# SAS_rev04.net
KiCad netlist of a schematic drawn in EAGLE
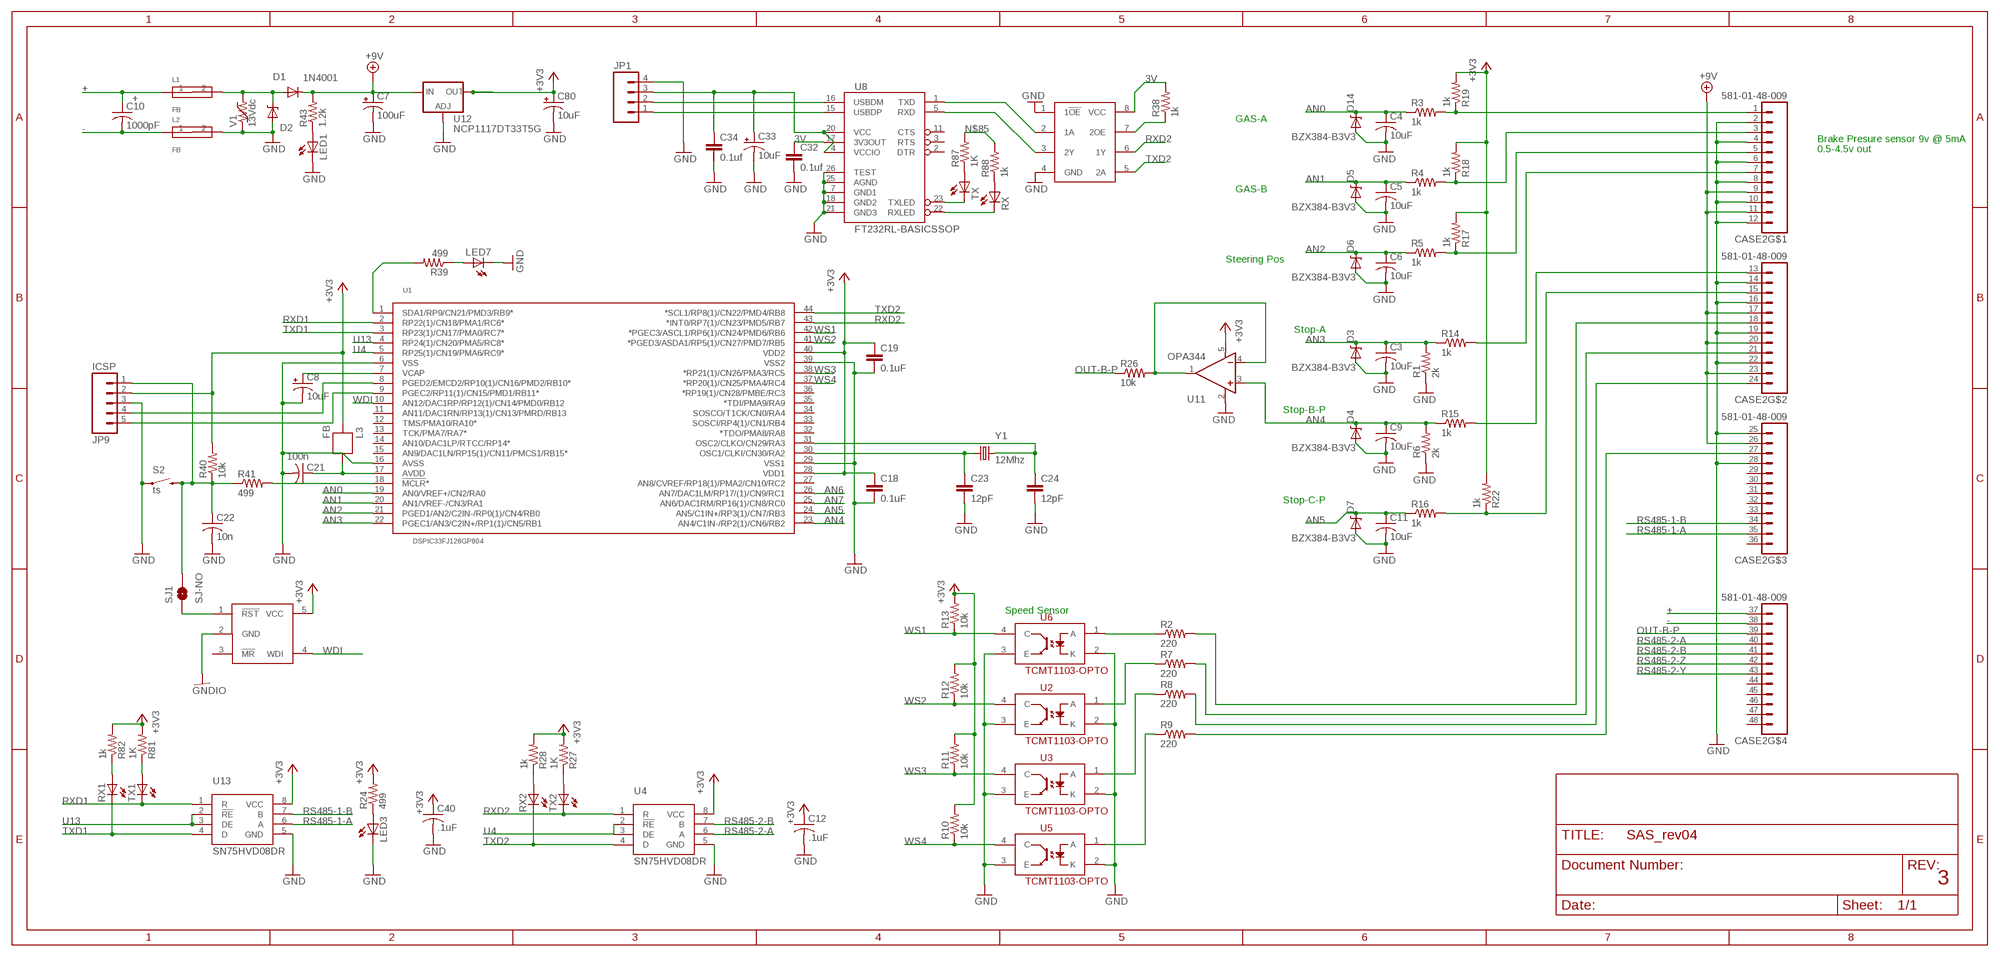
[diagram p0: schematic, sheet 1]

(export (version "E")
  (design (tool "Eeschema 10.0.6"))
  (components
    (comp (ref "C3")
      (value "10uF")
      (footprint "eagle-import:C0805")
      (libsource (lib "eagle-import") (part "C-USC0805"))
    )
    (comp (ref "C4")
      (value "10uF")
      (footprint "eagle-import:C0805")
      (libsource (lib "eagle-import") (part "C-USC0805"))
    )
    (comp (ref "C5")
      (value "10uF")
      (footprint "eagle-import:C0805")
      (libsource (lib "eagle-import") (part "C-USC0805"))
    )
    (comp (ref "C6")
      (value "10uF")
      (footprint "eagle-import:C0805")
      (libsource (lib "eagle-import") (part "C-USC0805"))
    )
    (comp (ref "C7")
      (value "100uF")
      (footprint "eagle-import:EIA7343")
      (libsource (lib "eagle-import") (part "SparkFun-Capacitors_CAP_POL7343"))
    )
    (comp (ref "C8")
      (value "10uF")
      (footprint "eagle-import:EIA3216")
      (libsource (lib "eagle-import") (part "10UF-TANT"))
    )
    (comp (ref "C9")
      (value "10uF")
      (footprint "eagle-import:C0805")
      (libsource (lib "eagle-import") (part "C-USC0805"))
    )
    (comp (ref "C10")
      (value "1000pF")
      (footprint "eagle-import:C1825")
      (libsource (lib "eagle-import") (part "C-USC1825"))
    )
    (comp (ref "C11")
      (value "10uF")
      (footprint "eagle-import:C0805")
      (libsource (lib "eagle-import") (part "C-USC0805"))
    )
    (comp (ref "C12")
      (value ".1uF")
      (footprint "eagle-import:C0805")
      (libsource (lib "eagle-import") (part "C-USC0805"))
    )
    (comp (ref "C18")
      (value "0.1uF")
      (footprint "eagle-import:0805")
      (libsource (lib "eagle-import") (part "SparkFun-Capacitors_CAP0805"))
    )
    (comp (ref "C19")
      (value "0.1uF")
      (footprint "eagle-import:0805")
      (libsource (lib "eagle-import") (part "SparkFun-Capacitors_CAP0805"))
    )
    (comp (ref "C21")
      (value "100n")
      (footprint "eagle-import:C0805")
      (libsource (lib "eagle-import") (part "C-USC0805"))
    )
    (comp (ref "C22")
      (value "10n")
      (footprint "eagle-import:C0805")
      (libsource (lib "eagle-import") (part "C-USC0805"))
    )
    (comp (ref "C23")
      (value "12pF")
      (footprint "eagle-import:0805")
      (libsource (lib "eagle-import") (part "SparkFun-Capacitors_CAP0805"))
    )
    (comp (ref "C24")
      (value "12pF")
      (footprint "eagle-import:0805")
      (libsource (lib "eagle-import") (part "SparkFun-Capacitors_CAP0805"))
    )
    (comp (ref "C32")
      (value "0.1uf")
      (footprint "eagle-import:0805")
      (libsource (lib "eagle-import") (part "CAP0805"))
    )
    (comp (ref "C33")
      (value "10uF")
      (footprint "eagle-import:EIA3216")
      (libsource (lib "eagle-import") (part "CAP_POL1206"))
    )
    (comp (ref "C34")
      (value "0.1uf")
      (footprint "eagle-import:0805")
      (libsource (lib "eagle-import") (part "CAP0805"))
    )
    (comp (ref "C40")
      (value ".1uF")
      (footprint "eagle-import:C0805")
      (libsource (lib "eagle-import") (part "C-USC0805"))
    )
    (comp (ref "C80")
      (value "10uF")
      (footprint "eagle-import:POLC1206")
      (libsource (lib "eagle-import") (part "POLCAP"))
    )
    (comp (ref "CASE2")
      (value "581-01-48-009")
      (footprint "eagle-import:581-01-48-009")
      (libsource (lib "eagle-import") (part "581-01-48-009"))
    )
    (comp (ref "D1")
      (value "1N4001")
      (footprint "eagle-import:SOD123")
      (libsource (lib "eagle-import") (part "DIODE-SOD123"))
    )
    (comp (ref "D2")
      (value "MM5Z30")
      (footprint "eagle-import:SOD-523F")
      (libsource (lib "eagle-import") (part "MM5Z30"))
    )
    (comp (ref "D3")
      (value "BZX384-B3V3")
      (footprint "eagle-import:SOD-323")
      (libsource (lib "eagle-import") (part "DIODE-ZENER-BZT52"))
    )
    (comp (ref "D4")
      (value "BZX384-B3V3")
      (footprint "eagle-import:SOD-323")
      (libsource (lib "eagle-import") (part "DIODE-ZENER-BZT52"))
    )
    (comp (ref "D5")
      (value "BZX384-B3V3")
      (footprint "eagle-import:SOD-323")
      (libsource (lib "eagle-import") (part "DIODE-ZENER-BZT52"))
    )
    (comp (ref "D6")
      (value "BZX384-B3V3")
      (footprint "eagle-import:SOD-323")
      (libsource (lib "eagle-import") (part "DIODE-ZENER-BZT52"))
    )
    (comp (ref "D7")
      (value "BZX384-B3V3")
      (footprint "eagle-import:SOD-323")
      (libsource (lib "eagle-import") (part "DIODE-ZENER-BZT52"))
    )
    (comp (ref "D14")
      (value "BZX384-B3V3")
      (footprint "eagle-import:SOD-323")
      (libsource (lib "eagle-import") (part "DIODE-ZENER-BZT52"))
    )
    (comp (ref "JP1")
      (value "M04POLAR")
      (footprint "eagle-import:MOLEX-1X4")
      (libsource (lib "eagle-import") (part "M04POLAR"))
    )
    (comp (ref "JP9")
      (value "ICSP")
      (footprint "eagle-import:1X05_LOCK_LONGPADS")
      (libsource (lib "eagle-import") (part "M05LOCK_LONGPADS"))
    )
    (comp (ref "L1")
      (value "FB")
      (footprint "eagle-import:0603")
      (libsource (lib "eagle-import") (part "FERITEBEAD"))
    )
    (comp (ref "L2")
      (value "FB")
      (footprint "eagle-import:0603")
      (libsource (lib "eagle-import") (part "FERITEBEAD"))
    )
    (comp (ref "L3")
      (value "FB")
      (footprint "eagle-import:0603")
      (libsource (lib "eagle-import") (part "FB"))
    )
    (comp (ref "LED1")
      (value "LEDCHIP-LED0805")
      (footprint "eagle-import:CHIP-LED0805")
      (libsource (lib "eagle-import") (part "LEDCHIP-LED0805"))
    )
    (comp (ref "LED3")
      (value "LEDCHIP-LED0805")
      (footprint "eagle-import:CHIP-LED0805")
      (libsource (lib "eagle-import") (part "LEDCHIP-LED0805"))
    )
    (comp (ref "LED7")
      (value "LEDCHIP-LED0805")
      (footprint "eagle-import:CHIP-LED0805")
      (libsource (lib "eagle-import") (part "LEDCHIP-LED0805"))
    )
    (comp (ref "R1")
      (value "2k")
      (footprint "eagle-import:R0805")
      (libsource (lib "eagle-import") (part "R-US_R0805"))
    )
    (comp (ref "R2")
      (value "220")
      (footprint "eagle-import:R0805")
      (libsource (lib "eagle-import") (part "R-US_R0805"))
    )
    (comp (ref "R3")
      (value "1k")
      (footprint "eagle-import:R0805")
      (libsource (lib "eagle-import") (part "R-US_R0805"))
    )
    (comp (ref "R4")
      (value "1k")
      (footprint "eagle-import:R0805")
      (libsource (lib "eagle-import") (part "R-US_R0805"))
    )
    (comp (ref "R5")
      (value "1k")
      (footprint "eagle-import:R0805")
      (libsource (lib "eagle-import") (part "R-US_R0805"))
    )
    (comp (ref "R6")
      (value "2k")
      (footprint "eagle-import:R0805")
      (libsource (lib "eagle-import") (part "R-US_R0805"))
    )
    (comp (ref "R7")
      (value "220")
      (footprint "eagle-import:R0805")
      (libsource (lib "eagle-import") (part "R-US_R0805"))
    )
    (comp (ref "R8")
      (value "220")
      (footprint "eagle-import:R0805")
      (libsource (lib "eagle-import") (part "R-US_R0805"))
    )
    (comp (ref "R9")
      (value "220")
      (footprint "eagle-import:R0805")
      (libsource (lib "eagle-import") (part "R-US_R0805"))
    )
    (comp (ref "R10")
      (value "10k")
      (footprint "eagle-import:R0805")
      (libsource (lib "eagle-import") (part "R-US_R0805"))
    )
    (comp (ref "R11")
      (value "10k")
      (footprint "eagle-import:R0805")
      (libsource (lib "eagle-import") (part "R-US_R0805"))
    )
    (comp (ref "R12")
      (value "10k")
      (footprint "eagle-import:R0805")
      (libsource (lib "eagle-import") (part "R-US_R0805"))
    )
    (comp (ref "R13")
      (value "10k")
      (footprint "eagle-import:R0805")
      (libsource (lib "eagle-import") (part "R-US_R0805"))
    )
    (comp (ref "R14")
      (value "1k")
      (footprint "eagle-import:R0805")
      (libsource (lib "eagle-import") (part "R-US_R0805"))
    )
    (comp (ref "R15")
      (value "1k")
      (footprint "eagle-import:R0805")
      (libsource (lib "eagle-import") (part "R-US_R0805"))
    )
    (comp (ref "R16")
      (value "1k")
      (footprint "eagle-import:R0805")
      (libsource (lib "eagle-import") (part "R-US_R0805"))
    )
    (comp (ref "R17")
      (value "1k")
      (footprint "eagle-import:R0805")
      (libsource (lib "eagle-import") (part "R-US_R0805"))
    )
    (comp (ref "R18")
      (value "1k")
      (footprint "eagle-import:R0805")
      (libsource (lib "eagle-import") (part "R-US_R0805"))
    )
    (comp (ref "R19")
      (value "1k")
      (footprint "eagle-import:R0805")
      (libsource (lib "eagle-import") (part "R-US_R0805"))
    )
    (comp (ref "R22")
      (value "1k")
      (footprint "eagle-import:R0805")
      (libsource (lib "eagle-import") (part "R-US_R0805"))
    )
    (comp (ref "R24")
      (value "499")
      (footprint "eagle-import:R0805")
      (libsource (lib "eagle-import") (part "R-US_R0805"))
    )
    (comp (ref "R26")
      (value "10k")
      (footprint "eagle-import:R0805")
      (libsource (lib "eagle-import") (part "R-US_R0805"))
    )
    (comp (ref "R27")
      (value "1K")
      (footprint "eagle-import:R0805")
      (libsource (lib "eagle-import") (part "R-US_R0805"))
    )
    (comp (ref "R28")
      (value "1k")
      (footprint "eagle-import:R0805")
      (libsource (lib "eagle-import") (part "R-US_R0805"))
    )
    (comp (ref "R38")
      (value "1k")
      (footprint "eagle-import:R0805")
      (libsource (lib "eagle-import") (part "R-US_R0805"))
    )
    (comp (ref "R39")
      (value "499")
      (footprint "eagle-import:0805")
      (libsource (lib "eagle-import") (part "RESISTOR0805-RES"))
    )
    (comp (ref "R40")
      (value "10k")
      (footprint "eagle-import:0805")
      (libsource (lib "eagle-import") (part "RESISTOR0805-RES"))
    )
    (comp (ref "R41")
      (value "499")
      (footprint "eagle-import:0805")
      (libsource (lib "eagle-import") (part "SparkFun-Resistors_RESISTOR0805-RES"))
    )
    (comp (ref "R43")
      (value "1.2k")
      (footprint "eagle-import:R0805")
      (libsource (lib "eagle-import") (part "R-US_R0805"))
    )
    (comp (ref "R81")
      (value "1K")
      (footprint "eagle-import:R0805")
      (libsource (lib "eagle-import") (part "R-US_R0805"))
    )
    (comp (ref "R82")
      (value "1k")
      (footprint "eagle-import:R0805")
      (libsource (lib "eagle-import") (part "R-US_R0805"))
    )
    (comp (ref "R87")
      (value "1K")
      (footprint "eagle-import:R0805")
      (libsource (lib "eagle-import") (part "R-US_R0805"))
    )
    (comp (ref "R88")
      (value "1k")
      (footprint "eagle-import:R0805")
      (libsource (lib "eagle-import") (part "R-US_R0805"))
    )
    (comp (ref "RX")
      (value "LEDCHIPLED_0805")
      (footprint "eagle-import:CHIPLED_0805")
      (libsource (lib "eagle-import") (part "LEDCHIPLED_0805"))
    )
    (comp (ref "RX1")
      (value "LEDCHIPLED_0805")
      (footprint "eagle-import:CHIPLED_0805")
      (libsource (lib "eagle-import") (part "LEDCHIPLED_0805"))
    )
    (comp (ref "RX2")
      (value "LEDCHIPLED_0805")
      (footprint "eagle-import:CHIPLED_0805")
      (libsource (lib "eagle-import") (part "LEDCHIPLED_0805"))
    )
    (comp (ref "S2")
      (value "ts")
      (footprint "eagle-import:TACTILE-PTH")
      (libsource (lib "eagle-import") (part "SWITCH-MOMENTARY-2PTH"))
    )
    (comp (ref "SJ1")
      (value "SJ-NO")
      (footprint "eagle-import:SJ_2S-NO")
      (libsource (lib "eagle-import") (part "SOLDERJUMPERNO"))
    )
    (comp (ref "TX")
      (value "LEDCHIPLED_0805")
      (footprint "eagle-import:CHIPLED_0805")
      (libsource (lib "eagle-import") (part "LEDCHIPLED_0805"))
    )
    (comp (ref "TX1")
      (value "LEDCHIPLED_0805")
      (footprint "eagle-import:CHIPLED_0805")
      (libsource (lib "eagle-import") (part "LEDCHIPLED_0805"))
    )
    (comp (ref "TX2")
      (value "LEDCHIPLED_0805")
      (footprint "eagle-import:CHIPLED_0805")
      (libsource (lib "eagle-import") (part "LEDCHIPLED_0805"))
    )
    (comp (ref "U1")
      (value "DSPIC33FJ128GP804")
      (footprint "eagle-import:TQFP-44")
      (libsource (lib "eagle-import") (part "DSPIC33FJ128GP804"))
    )
    (comp (ref "U2")
      (value "TCMT1103-OPTO")
      (footprint "eagle-import:SSOP-4")
      (libsource (lib "eagle-import") (part "TCMT1103-OPTO"))
    )
    (comp (ref "U3")
      (value "TCMT1103-OPTO")
      (footprint "eagle-import:SSOP-4")
      (libsource (lib "eagle-import") (part "TCMT1103-OPTO"))
    )
    (comp (ref "U4")
      (value "SN75HVD08DR")
      (footprint "eagle-import:SO-8")
      (libsource (lib "eagle-import") (part "SN75HVD08DR"))
    )
    (comp (ref "U5")
      (value "TCMT1103-OPTO")
      (footprint "eagle-import:SSOP-4")
      (libsource (lib "eagle-import") (part "TCMT1103-OPTO"))
    )
    (comp (ref "U6")
      (value "TCMT1103-OPTO")
      (footprint "eagle-import:SSOP-4")
      (libsource (lib "eagle-import") (part "TCMT1103-OPTO"))
    )
    (comp (ref "U8")
      (value "FT232RL-BASICSSOP")
      (footprint "eagle-import:SSOP28DB")
      (libsource (lib "eagle-import") (part "FT232RL-BASICSSOP"))
    )
    (comp (ref "U9")
      (value "MAX823")
      (footprint "eagle-import:SOT23-5L")
      (libsource (lib "eagle-import") (part "MAX823"))
    )
    (comp (ref "U11")
      (value "OPA344")
      (footprint "eagle-import:SOT23-5")
      (libsource (lib "eagle-import") (part "OPA344"))
    )
    (comp (ref "U12")
      (value "NCP1117DT33T5G")
      (footprint "eagle-import:V-REG_DPACK")
      (libsource (lib "eagle-import") (part "V_REG_317DPACK"))
    )
    (comp (ref "U13")
      (value "SN75HVD08DR")
      (footprint "eagle-import:SO-8")
      (libsource (lib "eagle-import") (part "SN75HVD08DR"))
    )
    (comp (ref "U14")
      (value "SN74LVC2G241DCTR")
      (footprint "eagle-import:VFSOP-8")
      (libsource (lib "eagle-import") (part "SN74LVC2G241DCTR"))
    )
    (comp (ref "V1")
      (value "13Vdc")
      (footprint "eagle-import:0603")
      (libsource (lib "eagle-import") (part "VAR-RES"))
    )
    (comp (ref "Y1")
      (value "12Mhz")
      (footprint "eagle-import:CRYSTAL-SMD-5X3")
      (libsource (lib "eagle-import") (part "CRYSTAL5X3"))
    )
  )
  (nets
    (net (code "1") (name "+3V3") (class "Default")
      (node (ref "C12") (pin "1") (pinfunction "1_1") (pintype "passive"))
      (node (ref "C18") (pin "1") (pinfunction "1_1") (pintype "passive"))
      (node (ref "C19") (pin "1") (pinfunction "1_1") (pintype "passive"))
      (node (ref "C40") (pin "1") (pinfunction "1_1") (pintype "passive"))
      (node (ref "C80") (pin "1") (pinfunction "+_1") (pintype "passive"))
      (node (ref "JP9") (pin "2") (pinfunction "2_2") (pintype "passive"))
      (node (ref "L3") (pin "2") (pinfunction "P$2_2") (pintype "bidirectional"))
      (node (ref "R10") (pin "2") (pinfunction "2_2") (pintype "passive"))
      (node (ref "R11") (pin "2") (pinfunction "2_2") (pintype "passive"))
      (node (ref "R12") (pin "2") (pinfunction "2_2") (pintype "passive"))
      (node (ref "R13") (pin "2") (pinfunction "2_2") (pintype "passive"))
      (node (ref "R17") (pin "2") (pinfunction "2_2") (pintype "passive"))
      (node (ref "R18") (pin "2") (pinfunction "2_2") (pintype "passive"))
      (node (ref "R19") (pin "2") (pinfunction "2_2") (pintype "passive"))
      (node (ref "R22") (pin "2") (pinfunction "2_2") (pintype "passive"))
      (node (ref "R24") (pin "2") (pinfunction "2_2") (pintype "passive"))
      (node (ref "R27") (pin "2") (pinfunction "2_2") (pintype "passive"))
      (node (ref "R28") (pin "2") (pinfunction "2_2") (pintype "passive"))
      (node (ref "R40") (pin "2") (pinfunction "2_2") (pintype "passive"))
      (node (ref "R81") (pin "2") (pinfunction "2_2") (pintype "passive"))
      (node (ref "R82") (pin "2") (pinfunction "2_2") (pintype "passive"))
      (node (ref "U1") (pin "28") (pinfunction "VDD1_28") (pintype "bidirectional"))
      (node (ref "U1") (pin "40") (pinfunction "VDD2_40") (pintype "bidirectional"))
      (node (ref "U11") (pin "5") (pinfunction "V+_5") (pintype "power_in"))
      (node (ref "U12") (pin "4") (pinfunction "OUT_4") (pintype "output"))
      (node (ref "U13") (pin "8") (pinfunction "VCC_8") (pintype "bidirectional"))
      (node (ref "U4") (pin "8") (pinfunction "VCC_8") (pintype "bidirectional"))
      (node (ref "U9") (pin "5") (pinfunction "VCC_5") (pintype "bidirectional"))
    )
    (net (code "2") (name "+9V") (class "Default")
      (node (ref "C7") (pin "A") (pinfunction "+_A") (pintype "passive"))
      (node (ref "CASE2") (pin "11") (pinfunction "11_11") (pintype "passive"))
      (node (ref "CASE2") (pin "17") (pinfunction "5_17") (pintype "passive"))
      (node (ref "CASE2") (pin "20") (pinfunction "8_20") (pintype "passive"))
      (node (ref "CASE2") (pin "23") (pinfunction "11_23") (pintype "passive"))
      (node (ref "CASE2") (pin "26") (pinfunction "2_26") (pintype "passive"))
      (node (ref "CASE2") (pin "9") (pinfunction "9_9") (pintype "passive"))
      (node (ref "D1") (pin "C") (pinfunction "C_C") (pintype "passive"))
      (node (ref "R43") (pin "2") (pinfunction "2_2") (pintype "passive"))
      (node (ref "U12") (pin "3") (pinfunction "IN_3") (pintype "input"))
    )
    (net (code "3") (name "/+") (class "Default")
      (node (ref "C10") (pin "1") (pinfunction "1_1") (pintype "passive"))
      (node (ref "CASE2") (pin "37") (pinfunction "1_37") (pintype "passive"))
      (node (ref "L1") (pin "1") (pinfunction "P$1_1") (pintype "bidirectional"))
    )
    (net (code "4") (name "/-") (class "Default")
      (node (ref "C10") (pin "2") (pinfunction "2_2") (pintype "passive"))
      (node (ref "CASE2") (pin "38") (pinfunction "2_38") (pintype "passive"))
      (node (ref "L2") (pin "1") (pinfunction "P$1_1") (pintype "bidirectional"))
    )
    (net (code "5") (name "/3V") (class "Default")
      (node (ref "C32") (pin "1") (pinfunction "1_1") (pintype "passive"))
      (node (ref "R38") (pin "2") (pinfunction "2_2") (pintype "passive"))
      (node (ref "U14") (pin "8") (pinfunction "VCC_8") (pintype "bidirectional"))
      (node (ref "U8") (pin "17") (pinfunction "3V3OUT_17") (pintype "output"))
    )
    (net (code "6") (name "/AN0") (class "Default")
      (node (ref "C4") (pin "1") (pinfunction "1_1") (pintype "passive"))
      (node (ref "D14") (pin "1") (pinfunction "C_1") (pintype "passive"))
      (node (ref "R3") (pin "1") (pinfunction "1_1") (pintype "passive"))
      (node (ref "U1") (pin "19") (pinfunction "AN0/VREF+/CN2/RA0_19") (pintype "bidirectional"))
    )
    (net (code "7") (name "/AN1") (class "Default")
      (node (ref "C5") (pin "1") (pinfunction "1_1") (pintype "passive"))
      (node (ref "D5") (pin "1") (pinfunction "C_1") (pintype "passive"))
      (node (ref "R4") (pin "1") (pinfunction "1_1") (pintype "passive"))
      (node (ref "U1") (pin "20") (pinfunction "AN1/VREF-/CN3/RA1_20") (pintype "bidirectional"))
    )
    (net (code "8") (name "/AN2") (class "Default")
      (node (ref "C6") (pin "1") (pinfunction "1_1") (pintype "passive"))
      (node (ref "D6") (pin "1") (pinfunction "C_1") (pintype "passive"))
      (node (ref "R5") (pin "1") (pinfunction "1_1") (pintype "passive"))
      (node (ref "U1") (pin "21") (pinfunction "PGED1/AN2/C2IN-/RP0(1)/CN4/RB0_21") (pintype "bidirectional"))
    )
    (net (code "9") (name "/AN3") (class "Default")
      (node (ref "C3") (pin "1") (pinfunction "1_1") (pintype "passive"))
      (node (ref "D3") (pin "1") (pinfunction "C_1") (pintype "passive"))
      (node (ref "R1") (pin "2") (pinfunction "2_2") (pintype "passive"))
      (node (ref "R14") (pin "1") (pinfunction "1_1") (pintype "passive"))
      (node (ref "U1") (pin "22") (pinfunction "PGEC1/AN3/C2IN+/RP1(1)/CN5/RB1_22") (pintype "bidirectional"))
    )
    (net (code "10") (name "/AN4") (class "Default")
      (node (ref "C9") (pin "1") (pinfunction "1_1") (pintype "passive"))
      (node (ref "D4") (pin "1") (pinfunction "C_1") (pintype "passive"))
      (node (ref "R15") (pin "1") (pinfunction "1_1") (pintype "passive"))
      (node (ref "R6") (pin "2") (pinfunction "2_2") (pintype "passive"))
      (node (ref "U1") (pin "23") (pinfunction "AN4/C1IN-/RP2(1)/CN6/RB2_23") (pintype "bidirectional"))
      (node (ref "U11") (pin "3") (pinfunction "+IN_3") (pintype "input"))
    )
    (net (code "11") (name "/AN5") (class "Default")
      (node (ref "C11") (pin "1") (pinfunction "1_1") (pintype "passive"))
      (node (ref "D7") (pin "1") (pinfunction "C_1") (pintype "passive"))
      (node (ref "R16") (pin "1") (pinfunction "1_1") (pintype "passive"))
      (node (ref "U1") (pin "24") (pinfunction "AN5/C1IN+/RP3(1)/CN7/RB3_24") (pintype "bidirectional"))
    )
    (net (code "12") (name "/AN6") (class "Default")
      (node (ref "U1") (pin "26") (pinfunction "AN7/DAC1LM/RP17/(1)/CN9/RC1_26") (pintype "bidirectional"))
    )
    (net (code "13") (name "/AN7") (class "Default")
      (node (ref "U1") (pin "25") (pinfunction "AN6/DAC1RM/RP16(1)/CN8/RC0_25") (pintype "bidirectional"))
    )
    (net (code "14") (name "/N$85") (class "Default")
      (node (ref "C33") (pin "A") (pinfunction "+_A") (pintype "passive"))
      (node (ref "C34") (pin "1") (pinfunction "1_1") (pintype "passive"))
      (node (ref "JP1") (pin "3") (pinfunction "3_3") (pintype "passive"))
      (node (ref "R87") (pin "2") (pinfunction "2_2") (pintype "passive"))
      (node (ref "R88") (pin "2") (pinfunction "2_2") (pintype "passive"))
      (node (ref "U8") (pin "20") (pinfunction "VCC_20") (pintype "power_in"))
      (node (ref "U8") (pin "4") (pinfunction "VCCIO_4") (pintype "power_in"))
    )
    (net (code "15") (name "/OUT-B-P") (class "Default")
      (node (ref "CASE2") (pin "39") (pinfunction "3_39") (pintype "passive"))
      (node (ref "R26") (pin "1") (pinfunction "1_1") (pintype "passive"))
    )
    (net (code "16") (name "/RS485-1-A") (class "Default")
      (node (ref "CASE2") (pin "35") (pinfunction "11_35") (pintype "passive"))
      (node (ref "U13") (pin "6") (pinfunction "A_6") (pintype "bidirectional"))
    )
    (net (code "17") (name "/RS485-1-B") (class "Default")
      (node (ref "CASE2") (pin "34") (pinfunction "10_34") (pintype "passive"))
      (node (ref "U13") (pin "7") (pinfunction "B_7") (pintype "bidirectional"))
    )
    (net (code "18") (name "/RS485-2-A") (class "Default")
      (node (ref "CASE2") (pin "40") (pinfunction "4_40") (pintype "passive"))
      (node (ref "U4") (pin "6") (pinfunction "A_6") (pintype "bidirectional"))
    )
    (net (code "19") (name "/RS485-2-B") (class "Default")
      (node (ref "CASE2") (pin "41") (pinfunction "5_41") (pintype "passive"))
      (node (ref "U4") (pin "7") (pinfunction "B_7") (pintype "bidirectional"))
    )
    (net (code "20") (name "/RS485-2-Y") (class "Default")
      (node (ref "CASE2") (pin "43") (pinfunction "7_43") (pintype "passive"))
    )
    (net (code "21") (name "/RS485-2-Z") (class "Default")
      (node (ref "CASE2") (pin "42") (pinfunction "6_42") (pintype "passive"))
    )
    (net (code "22") (name "/RXD1") (class "Default")
      (node (ref "TX1") (pin "C") (pinfunction "C_C") (pintype "passive"))
      (node (ref "U1") (pin "2") (pinfunction "RP22(1)/CN18/PMA1/RC6*_2") (pintype "bidirectional"))
      (node (ref "U13") (pin "1") (pinfunction "R_1") (pintype "bidirectional"))
    )
    (net (code "23") (name "/RXD2") (class "Default")
      (node (ref "TX2") (pin "C") (pinfunction "C_C") (pintype "passive"))
      (node (ref "U1") (pin "43") (pinfunction "*INT0/RP7(1)/CN23/PMD5/RB7_43") (pintype "bidirectional"))
      (node (ref "U14") (pin "6") (pinfunction "1Y_6") (pintype "bidirectional"))
      (node (ref "U4") (pin "1") (pinfunction "R_1") (pintype "bidirectional"))
    )
    (net (code "24") (name "/TXD1") (class "Default")
      (node (ref "RX1") (pin "C") (pinfunction "C_C") (pintype "passive"))
      (node (ref "U1") (pin "3") (pinfunction "RP23(1)/CN17/PMA0/RC7*_3") (pintype "bidirectional"))
      (node (ref "U13") (pin "4") (pinfunction "D_4") (pintype "bidirectional"))
    )
    (net (code "25") (name "/TXD2") (class "Default")
      (node (ref "RX2") (pin "C") (pinfunction "C_C") (pintype "passive"))
      (node (ref "U1") (pin "44") (pinfunction "*SCL1/RP8(1)/CN22/PMD4/RB8_44") (pintype "bidirectional"))
      (node (ref "U14") (pin "5") (pinfunction "2A_5") (pintype "bidirectional"))
      (node (ref "U4") (pin "4") (pinfunction "D_4") (pintype "bidirectional"))
    )
    (net (code "26") (name "/U4") (class "Default")
      (node (ref "U1") (pin "5") (pinfunction "RP25(1)/CN19/PMA6/RC9*_5") (pintype "bidirectional"))
      (node (ref "U4") (pin "2") (pinfunction "~{RE}_2") (pintype "bidirectional"))
      (node (ref "U4") (pin "3") (pinfunction "DE_3") (pintype "bidirectional"))
    )
    (net (code "27") (name "/U13") (class "Default")
      (node (ref "U1") (pin "4") (pinfunction "RP24(1)/CN20/PMA5/RC8*_4") (pintype "bidirectional"))
      (node (ref "U13") (pin "2") (pinfunction "~{RE}_2") (pintype "bidirectional"))
      (node (ref "U13") (pin "3") (pinfunction "DE_3") (pintype "bidirectional"))
    )
    (net (code "28") (name "/WDI") (class "Default")
      (node (ref "U1") (pin "10") (pinfunction "AN12/DAC1RP/RP12(1)/CN14/PMD0/RB12_10") (pintype "bidirectional"))
      (node (ref "U9") (pin "4") (pinfunction "WDI_4") (pintype "bidirectional"))
    )
    (net (code "29") (name "/WS1") (class "Default")
      (node (ref "R13") (pin "1") (pinfunction "1_1") (pintype "passive"))
      (node (ref "U1") (pin "42") (pinfunction "*PGEC3/ASCL1/RP6(1)/CN24/PMD6/RB6_42") (pintype "bidirectional"))
      (node (ref "U6") (pin "4") (pinfunction "C_4") (pintype "bidirectional"))
    )
    (net (code "30") (name "/WS2") (class "Default")
      (node (ref "R12") (pin "1") (pinfunction "1_1") (pintype "passive"))
      (node (ref "U1") (pin "41") (pinfunction "*PGED3/ASDA1/RP5(1)/CN27/PMD7/RB5_41") (pintype "bidirectional"))
      (node (ref "U2") (pin "4") (pinfunction "C_4") (pintype "bidirectional"))
    )
    (net (code "31") (name "/WS3") (class "Default")
      (node (ref "R11") (pin "1") (pinfunction "1_1") (pintype "passive"))
      (node (ref "U1") (pin "38") (pinfunction "*RP21(1)/CN26/PMA3/RC5_38") (pintype "bidirectional"))
      (node (ref "U3") (pin "4") (pinfunction "C_4") (pintype "bidirectional"))
    )
    (net (code "32") (name "/WS4") (class "Default")
      (node (ref "R10") (pin "1") (pinfunction "1_1") (pintype "passive"))
      (node (ref "U1") (pin "37") (pinfunction "*RP20(1)/CN25/PMA4/RC4_37") (pintype "bidirectional"))
      (node (ref "U5") (pin "4") (pinfunction "C_4") (pintype "bidirectional"))
    )
    (net (code "33") (name "GND") (class "Default")
      (node (ref "C11") (pin "2") (pinfunction "2_2") (pintype "passive"))
      (node (ref "C12") (pin "2") (pinfunction "2_2") (pintype "passive"))
      (node (ref "C18") (pin "2") (pinfunction "2_2") (pintype "passive"))
      (node (ref "C19") (pin "2") (pinfunction "2_2") (pintype "passive"))
      (node (ref "C21") (pin "2") (pinfunction "2_2") (pintype "passive"))
      (node (ref "C22") (pin "2") (pinfunction "2_2") (pintype "passive"))
      (node (ref "C23") (pin "2") (pinfunction "2_2") (pintype "passive"))
      (node (ref "C24") (pin "2") (pinfunction "2_2") (pintype "passive"))
      (node (ref "C3") (pin "2") (pinfunction "2_2") (pintype "passive"))
      (node (ref "C32") (pin "2") (pinfunction "2_2") (pintype "passive"))
      (node (ref "C33") (pin "C") (pinfunction "-_C") (pintype "passive"))
      (node (ref "C34") (pin "2") (pinfunction "2_2") (pintype "passive"))
      (node (ref "C4") (pin "2") (pinfunction "2_2") (pintype "passive"))
      (node (ref "C40") (pin "2") (pinfunction "2_2") (pintype "passive"))
      (node (ref "C5") (pin "2") (pinfunction "2_2") (pintype "passive"))
      (node (ref "C6") (pin "2") (pinfunction "2_2") (pintype "passive"))
      (node (ref "C7") (pin "C") (pinfunction "-_C") (pintype "passive"))
      (node (ref "C8") (pin "C") (pinfunction "-_C") (pintype "passive"))
      (node (ref "C80") (pin "2") (pinfunction "-_2") (pintype "passive"))
      (node (ref "C9") (pin "2") (pinfunction "2_2") (pintype "passive"))
      (node (ref "CASE2") (pin "10") (pinfunction "10_10") (pintype "passive"))
      (node (ref "CASE2") (pin "12") (pinfunction "12_12") (pintype "passive"))
      (node (ref "CASE2") (pin "14") (pinfunction "2_14") (pintype "passive"))
      (node (ref "CASE2") (pin "16") (pinfunction "4_16") (pintype "passive"))
      (node (ref "CASE2") (pin "19") (pinfunction "7_19") (pintype "passive"))
      (node (ref "CASE2") (pin "2") (pinfunction "2_2") (pintype "passive"))
      (node (ref "CASE2") (pin "22") (pinfunction "10_22") (pintype "passive"))
      (node (ref "CASE2") (pin "25") (pinfunction "1_25") (pintype "passive"))
      (node (ref "CASE2") (pin "28") (pinfunction "4_28") (pintype "passive"))
      (node (ref "CASE2") (pin "4") (pinfunction "4_4") (pintype "passive"))
      (node (ref "CASE2") (pin "6") (pinfunction "6_6") (pintype "passive"))
      (node (ref "CASE2") (pin "8") (pinfunction "8_8") (pintype "passive"))
      (node (ref "D14") (pin "2") (pinfunction "A_2") (pintype "passive"))
      (node (ref "D2") (pin "A") (pinfunction "A_A") (pintype "passive"))
      (node (ref "D3") (pin "2") (pinfunction "A_2") (pintype "passive"))
      (node (ref "D4") (pin "2") (pinfunction "A_2") (pintype "passive"))
      (node (ref "D5") (pin "2") (pinfunction "A_2") (pintype "passive"))
      (node (ref "D6") (pin "2") (pinfunction "A_2") (pintype "passive"))
      (node (ref "D7") (pin "2") (pinfunction "A_2") (pintype "passive"))
      (node (ref "JP1") (pin "4") (pinfunction "4_4") (pintype "passive"))
      (node (ref "JP9") (pin "3") (pinfunction "3_3") (pintype "passive"))
      (node (ref "L2") (pin "2") (pinfunction "P$2_2") (pintype "bidirectional"))
      (node (ref "LED1") (pin "C") (pinfunction "C_C") (pintype "passive"))
      (node (ref "LED3") (pin "C") (pinfunction "C_C") (pintype "passive"))
      (node (ref "LED7") (pin "C") (pinfunction "C_C") (pintype "passive"))
      (node (ref "R1") (pin "1") (pinfunction "1_1") (pintype "passive"))
      (node (ref "R6") (pin "1") (pinfunction "1_1") (pintype "passive"))
      (node (ref "S2") (pin "1") (pinfunction "1_1") (pintype "passive"))
      (node (ref "U1") (pin "16") (pinfunction "AVSS_16") (pintype "bidirectional"))
      (node (ref "U1") (pin "29") (pinfunction "VSS1_29") (pintype "bidirectional"))
      (node (ref "U1") (pin "39") (pinfunction "VSS2_39") (pintype "bidirectional"))
      (node (ref "U1") (pin "6") (pinfunction "VSS_6") (pintype "bidirectional"))
      (node (ref "U11") (pin "2") (pinfunction "V-_2") (pintype "power_in"))
      (node (ref "U12") (pin "1") (pinfunction "ADJ_1") (pintype "input"))
      (node (ref "U13") (pin "5") (pinfunction "GND_5") (pintype "bidirectional"))
      (node (ref "U14") (pin "1") (pinfunction "1~{OE}_1") (pintype "bidirectional"))
      (node (ref "U14") (pin "4") (pinfunction "GND_4") (pintype "bidirectional"))
      (node (ref "U2") (pin "2") (pinfunction "K_2") (pintype "bidirectional"))
      (node (ref "U2") (pin "3") (pinfunction "E_3") (pintype "bidirectional"))
      (node (ref "U3") (pin "2") (pinfunction "K_2") (pintype "bidirectional"))
      (node (ref "U3") (pin "3") (pinfunction "E_3") (pintype "bidirectional"))
      (node (ref "U4") (pin "5") (pinfunction "GND_5") (pintype "bidirectional"))
      (node (ref "U5") (pin "2") (pinfunction "K_2") (pintype "bidirectional"))
      (node (ref "U5") (pin "3") (pinfunction "E_3") (pintype "bidirectional"))
      (node (ref "U6") (pin "2") (pinfunction "K_2") (pintype "bidirectional"))
      (node (ref "U6") (pin "3") (pinfunction "E_3") (pintype "bidirectional"))
      (node (ref "U8") (pin "18") (pinfunction "GND2_18") (pintype "power_in"))
      (node (ref "U8") (pin "21") (pinfunction "GND3_21") (pintype "power_in"))
      (node (ref "U8") (pin "25") (pinfunction "AGND_25") (pintype "power_in"))
      (node (ref "U8") (pin "26") (pinfunction "TEST_26") (pintype "input"))
      (node (ref "U8") (pin "7") (pinfunction "GND1_7") (pintype "power_in"))
      (node (ref "V1") (pin "1") (pinfunction "1_1") (pintype "passive"))
    )
    (net (code "34") (name "GNDIO") (class "Default")
      (node (ref "U9") (pin "2") (pinfunction "GND_2") (pintype "bidirectional"))
    )
    (net (code "35") (name "Net-(C8-+)") (class "Default")
      (node (ref "C8") (pin "A") (pinfunction "+_A") (pintype "passive"))
      (node (ref "U1") (pin "7") (pinfunction "VCAP_7") (pintype "bidirectional"))
    )
    (net (code "36") (name "Net-(CASE2-Pad1)") (class "Default")
      (node (ref "CASE2") (pin "1") (pinfunction "1_1") (pintype "passive"))
      (node (ref "R19") (pin "1") (pinfunction "1_1") (pintype "passive"))
      (node (ref "R3") (pin "2") (pinfunction "2_2") (pintype "passive"))
    )
    (net (code "37") (name "Net-(CASE2-Pad3)") (class "Default")
      (node (ref "CASE2") (pin "3") (pinfunction "3_3") (pintype "passive"))
      (node (ref "R18") (pin "1") (pinfunction "1_1") (pintype "passive"))
      (node (ref "R4") (pin "2") (pinfunction "2_2") (pintype "passive"))
    )
    (net (code "38") (name "Net-(CASE2-Pad5)") (class "Default")
      (node (ref "CASE2") (pin "5") (pinfunction "5_5") (pintype "passive"))
      (node (ref "R17") (pin "1") (pinfunction "1_1") (pintype "passive"))
      (node (ref "R5") (pin "2") (pinfunction "2_2") (pintype "passive"))
    )
    (net (code "39") (name "Net-(CASE2-Pad7)") (class "Default")
      (node (ref "CASE2") (pin "7") (pinfunction "7_7") (pintype "passive"))
      (node (ref "R14") (pin "2") (pinfunction "2_2") (pintype "passive"))
    )
    (net (code "40") (name "Net-(CASE2B-1)") (class "Default")
      (node (ref "CASE2") (pin "13") (pinfunction "1_13") (pintype "passive"))
      (node (ref "R15") (pin "2") (pinfunction "2_2") (pintype "passive"))
    )
    (net (code "41") (name "Net-(CASE2B-3)") (class "Default")
      (node (ref "CASE2") (pin "15") (pinfunction "3_15") (pintype "passive"))
      (node (ref "R16") (pin "2") (pinfunction "2_2") (pintype "passive"))
      (node (ref "R22") (pin "1") (pinfunction "1_1") (pintype "passive"))
    )
    (net (code "42") (name "Net-(CASE2B-6)") (class "Default")
      (node (ref "CASE2") (pin "18") (pinfunction "6_18") (pintype "passive"))
      (node (ref "R2") (pin "2") (pinfunction "2_2") (pintype "passive"))
    )
    (net (code "43") (name "Net-(CASE2B-9)") (class "Default")
      (node (ref "CASE2") (pin "21") (pinfunction "9_21") (pintype "passive"))
      (node (ref "R7") (pin "2") (pinfunction "2_2") (pintype "passive"))
    )
    (net (code "44") (name "Net-(CASE2B-12)") (class "Default")
      (node (ref "CASE2") (pin "24") (pinfunction "12_24") (pintype "passive"))
      (node (ref "R8") (pin "2") (pinfunction "2_2") (pintype "passive"))
    )
    (net (code "45") (name "Net-(CASE2C-3)") (class "Default")
      (node (ref "CASE2") (pin "27") (pinfunction "3_27") (pintype "passive"))
      (node (ref "R9") (pin "2") (pinfunction "2_2") (pintype "passive"))
    )
    (net (code "46") (name "Net-(L1-P$2)") (class "Default")
      (node (ref "D1") (pin "A") (pinfunction "A_A") (pintype "passive"))
      (node (ref "D2") (pin "C") (pinfunction "C_C") (pintype "passive"))
      (node (ref "L1") (pin "2") (pinfunction "P$2_2") (pintype "bidirectional"))
      (node (ref "V1") (pin "2") (pinfunction "2_2") (pintype "passive"))
    )
    (net (code "47") (name "Net-(L3-P$1)") (class "Default")
      (node (ref "C21") (pin "1") (pinfunction "1_1") (pintype "passive"))
      (node (ref "L3") (pin "1") (pinfunction "P$1_1") (pintype "bidirectional"))
      (node (ref "U1") (pin "17") (pinfunction "AVDD_17") (pintype "bidirectional"))
    )
    (net (code "48") (name "Net-(LED1-PadA)") (class "Default")
      (node (ref "LED1") (pin "A") (pinfunction "A_A") (pintype "passive"))
      (node (ref "R43") (pin "1") (pinfunction "1_1") (pintype "passive"))
    )
    (net (code "49") (name "Net-(LED3-PadA)") (class "Default")
      (node (ref "LED3") (pin "A") (pinfunction "A_A") (pintype "passive"))
      (node (ref "R24") (pin "1") (pinfunction "1_1") (pintype "passive"))
    )
    (net (code "50") (name "Net-(LED7-PadA)") (class "Default")
      (node (ref "LED7") (pin "A") (pinfunction "A_A") (pintype "passive"))
      (node (ref "R39") (pin "1") (pinfunction "1_1") (pintype "passive"))
    )
    (net (code "51") (name "Net-(R27-Pad1)") (class "Default")
      (node (ref "R27") (pin "1") (pinfunction "1_1") (pintype "passive"))
      (node (ref "TX2") (pin "A") (pinfunction "A_A") (pintype "passive"))
    )
    (net (code "52") (name "Net-(R28-Pad1)") (class "Default")
      (node (ref "R28") (pin "1") (pinfunction "1_1") (pintype "passive"))
      (node (ref "RX2") (pin "A") (pinfunction "A_A") (pintype "passive"))
    )
    (net (code "53") (name "Net-(R81-Pad1)") (class "Default")
      (node (ref "R81") (pin "1") (pinfunction "1_1") (pintype "passive"))
      (node (ref "TX1") (pin "A") (pinfunction "A_A") (pintype "passive"))
    )
    (net (code "54") (name "Net-(R82-Pad1)") (class "Default")
      (node (ref "R82") (pin "1") (pinfunction "1_1") (pintype "passive"))
      (node (ref "RX1") (pin "A") (pinfunction "A_A") (pintype "passive"))
    )
    (net (code "55") (name "Net-(R87-Pad1)") (class "Default")
      (node (ref "R87") (pin "1") (pinfunction "1_1") (pintype "passive"))
      (node (ref "TX") (pin "A") (pinfunction "A_A") (pintype "passive"))
    )
    (net (code "56") (name "Net-(R88-Pad1)") (class "Default")
      (node (ref "R88") (pin "1") (pinfunction "1_1") (pintype "passive"))
      (node (ref "RX") (pin "A") (pinfunction "A_A") (pintype "passive"))
    )
    (net (code "57") (name "Net-(S2-2)") (class "Default")
      (node (ref "C22") (pin "1") (pinfunction "1_1") (pintype "passive"))
      (node (ref "JP9") (pin "1") (pinfunction "1_1") (pintype "passive"))
      (node (ref "R40") (pin "1") (pinfunction "1_1") (pintype "passive"))
      (node (ref "R41") (pin "1") (pinfunction "1_1") (pintype "passive"))
      (node (ref "S2") (pin "3") (pinfunction "2_3") (pintype "passive"))
      (node (ref "SJ1") (pin "2") (pinfunction "2_2") (pintype "passive"))
    )
    (net (code "58") (name "Net-(U1-OSC1{slash}CLKI{slash}CN30{slash}RA2)") (class "Default")
      (node (ref "C23") (pin "1") (pinfunction "1_1") (pintype "passive"))
      (node (ref "U1") (pin "30") (pinfunction "OSC1/CLKI/CN30/RA2_30") (pintype "bidirectional"))
      (node (ref "Y1") (pin "1") (pinfunction "1_1") (pintype "passive"))
    )
    (net (code "59") (name "Net-(U1-OSC2{slash}CLKO{slash}CN29{slash}RA3)") (class "Default")
      (node (ref "C24") (pin "1") (pinfunction "1_1") (pintype "passive"))
      (node (ref "U1") (pin "31") (pinfunction "OSC2/CLKO/CN29/RA3_31") (pintype "bidirectional"))
      (node (ref "Y1") (pin "3") (pinfunction "2_3") (pintype "passive"))
    )
    (net (code "60") (name "Net-(U1-PGEC2{slash}RP11(1){slash}CN15{slash}PMD1{slash}RB11*)") (class "Default")
      (node (ref "JP9") (pin "5") (pinfunction "5_5") (pintype "passive"))
      (node (ref "U1") (pin "9") (pinfunction "PGEC2/RP11(1)/CN15/PMD1/RB11*_9") (pintype "bidirectional"))
    )
    (net (code "61") (name "Net-(U1-PGED2{slash}EMCD2{slash}RP10(1){slash}CN16{slash}PMD2{slash}RB10*)") (class "Default")
      (node (ref "JP9") (pin "4") (pinfunction "4_4") (pintype "passive"))
      (node (ref "U1") (pin "8") (pinfunction "PGED2/EMCD2/RP10(1)/CN16/PMD2/RB10*_8") (pintype "bidirectional"))
    )
    (net (code "62") (name "Net-(U1-SDA1{slash}RP9{slash}CN21{slash}PMD3{slash}RB9*)") (class "Default")
      (node (ref "R39") (pin "2") (pinfunction "2_2") (pintype "passive"))
      (node (ref "U1") (pin "1") (pinfunction "SDA1/RP9/CN21/PMD3/RB9*_1") (pintype "bidirectional"))
    )
    (net (code "63") (name "Net-(U1-~{MCLR}*)") (class "Default")
      (node (ref "R41") (pin "2") (pinfunction "2_2") (pintype "passive"))
      (node (ref "U1") (pin "18") (pinfunction "~{MCLR}*_18") (pintype "bidirectional"))
    )
    (net (code "64") (name "Net-(U2-A)") (class "Default")
      (node (ref "R7") (pin "1") (pinfunction "1_1") (pintype "passive"))
      (node (ref "U2") (pin "1") (pinfunction "A_1") (pintype "bidirectional"))
    )
    (net (code "65") (name "Net-(U3-A)") (class "Default")
      (node (ref "R8") (pin "1") (pinfunction "1_1") (pintype "passive"))
      (node (ref "U3") (pin "1") (pinfunction "A_1") (pintype "bidirectional"))
    )
    (net (code "66") (name "Net-(U5-A)") (class "Default")
      (node (ref "R9") (pin "1") (pinfunction "1_1") (pintype "passive"))
      (node (ref "U5") (pin "1") (pinfunction "A_1") (pintype "bidirectional"))
    )
    (net (code "67") (name "Net-(U6-A)") (class "Default")
      (node (ref "R2") (pin "1") (pinfunction "1_1") (pintype "passive"))
      (node (ref "U6") (pin "1") (pinfunction "A_1") (pintype "bidirectional"))
    )
    (net (code "68") (name "Net-(U8-RXLED)") (class "Default")
      (node (ref "RX") (pin "C") (pinfunction "C_C") (pintype "passive"))
      (node (ref "U8") (pin "22") (pinfunction "RXLED_22") (pintype "bidirectional"))
    )
    (net (code "69") (name "Net-(U8-TXLED)") (class "Default")
      (node (ref "TX") (pin "C") (pinfunction "C_C") (pintype "passive"))
      (node (ref "U8") (pin "23") (pinfunction "TXLED_23") (pintype "bidirectional"))
    )
    (net (code "70") (name "Net-(U8-USBDM)") (class "Default")
      (node (ref "JP1") (pin "2") (pinfunction "2_2") (pintype "passive"))
      (node (ref "U8") (pin "16") (pinfunction "USBDM_16") (pintype "bidirectional"))
    )
    (net (code "71") (name "Net-(U8-USBDP)") (class "Default")
      (node (ref "JP1") (pin "1") (pinfunction "1_1") (pintype "passive"))
      (node (ref "U8") (pin "15") (pinfunction "USBDP_15") (pintype "bidirectional"))
    )
    (net (code "72") (name "Net-(U9-~{RST})") (class "Default")
      (node (ref "SJ1") (pin "1") (pinfunction "1_1") (pintype "passive"))
      (node (ref "U9") (pin "1") (pinfunction "~{RST}_1") (pintype "bidirectional"))
    )
    (net (code "73") (name "Net-(U11--IN)") (class "Default")
      (node (ref "R26") (pin "2") (pinfunction "2_2") (pintype "passive"))
      (node (ref "U11") (pin "1") (pinfunction "OUT_1") (pintype "output"))
      (node (ref "U11") (pin "4") (pinfunction "-IN_4") (pintype "input"))
    )
    (net (code "74") (name "Net-(U14-1A)") (class "Default")
      (node (ref "U14") (pin "2") (pinfunction "1A_2") (pintype "bidirectional"))
      (node (ref "U8") (pin "1") (pinfunction "TXD_1") (pintype "output"))
    )
    (net (code "75") (name "Net-(U14-2OE)") (class "Default")
      (node (ref "R38") (pin "1") (pinfunction "1_1") (pintype "passive"))
      (node (ref "U14") (pin "7") (pinfunction "2OE_7") (pintype "bidirectional"))
    )
    (net (code "76") (name "Net-(U14-2Y)") (class "Default")
      (node (ref "U14") (pin "3") (pinfunction "2Y_3") (pintype "bidirectional"))
      (node (ref "U8") (pin "5") (pinfunction "RXD_5") (pintype "input"))
    )
    (net (code "77") (name "unconnected-(CASE2C-5-Pad29)") (class "Default")
      (node (ref "CASE2") (pin "29") (pinfunction "5_29") (pintype "passive"))
    )
    (net (code "78") (name "unconnected-(CASE2C-6-Pad30)") (class "Default")
      (node (ref "CASE2") (pin "30") (pinfunction "6_30") (pintype "passive"))
    )
    (net (code "79") (name "unconnected-(CASE2C-7-Pad31)") (class "Default")
      (node (ref "CASE2") (pin "31") (pinfunction "7_31") (pintype "passive"))
    )
    (net (code "80") (name "unconnected-(CASE2C-8-Pad32)") (class "Default")
      (node (ref "CASE2") (pin "32") (pinfunction "8_32") (pintype "passive"))
    )
    (net (code "81") (name "unconnected-(CASE2C-9-Pad33)") (class "Default")
      (node (ref "CASE2") (pin "33") (pinfunction "9_33") (pintype "passive"))
    )
    (net (code "82") (name "unconnected-(CASE2C-12-Pad36)") (class "Default")
      (node (ref "CASE2") (pin "36") (pinfunction "12_36") (pintype "passive"))
    )
    (net (code "83") (name "unconnected-(CASE2D-8-Pad44)") (class "Default")
      (node (ref "CASE2") (pin "44") (pinfunction "8_44") (pintype "passive"))
    )
    (net (code "84") (name "unconnected-(CASE2D-9-Pad45)") (class "Default")
      (node (ref "CASE2") (pin "45") (pinfunction "9_45") (pintype "passive"))
    )
    (net (code "85") (name "unconnected-(CASE2D-10-Pad46)") (class "Default")
      (node (ref "CASE2") (pin "46") (pinfunction "10_46") (pintype "passive"))
    )
    (net (code "86") (name "unconnected-(CASE2D-11-Pad47)") (class "Default")
      (node (ref "CASE2") (pin "47") (pinfunction "11_47") (pintype "passive"))
    )
    (net (code "87") (name "unconnected-(CASE2D-12-Pad48)") (class "Default")
      (node (ref "CASE2") (pin "48") (pinfunction "12_48") (pintype "passive"))
    )
    (net (code "88") (name "unconnected-(U1-*RP19(1){slash}CN28{slash}PMBE{slash}RC3-Pad36)") (class "Default")
      (node (ref "U1") (pin "36") (pinfunction "*RP19(1)/CN28/PMBE/RC3_36") (pintype "bidirectional"))
    )
    (net (code "89") (name "unconnected-(U1-*TDI{slash}PMA9{slash}RA9-Pad35)") (class "Default")
      (node (ref "U1") (pin "35") (pinfunction "*TDI/PMA9/RA9_35") (pintype "bidirectional"))
    )
    (net (code "90") (name "unconnected-(U1-*TDO{slash}PMA8{slash}RA8-Pad32)") (class "Default")
      (node (ref "U1") (pin "32") (pinfunction "*TDO/PMA8/RA8_32") (pintype "bidirectional"))
    )
    (net (code "91") (name "unconnected-(U1-AN8{slash}CVREF{slash}RP18(1){slash}PMA2{slash}CN10{slash}RC2-Pad27)") (class "Default")
      (node (ref "U1") (pin "27") (pinfunction "AN8/CVREF/RP18(1)/PMA2/CN10/RC2_27") (pintype "bidirectional"))
    )
    (net (code "92") (name "unconnected-(U1-AN9{slash}DAC1LN{slash}RP15(1){slash}CN11{slash}PMCS1{slash}RB15*-Pad15)") (class "Default")
      (node (ref "U1") (pin "15") (pinfunction "AN9/DAC1LN/RP15(1)/CN11/PMCS1/RB15*_15") (pintype "bidirectional"))
    )
    (net (code "93") (name "unconnected-(U1-AN10{slash}DAC1LP{slash}RTCC{slash}RP14*-Pad14)") (class "Default")
      (node (ref "U1") (pin "14") (pinfunction "AN10/DAC1LP/RTCC/RP14*_14") (pintype "bidirectional"))
    )
    (net (code "94") (name "unconnected-(U1-AN11{slash}DAC1RN{slash}RP13(1){slash}CN13{slash}PMRD{slash}RB13-Pad11)") (class "Default")
      (node (ref "U1") (pin "11") (pinfunction "AN11/DAC1RN/RP13(1)/CN13/PMRD/RB13_11") (pintype "bidirectional"))
    )
    (net (code "95") (name "unconnected-(U1-SOSCI{slash}RP4(1){slash}CN1{slash}RB4-Pad33)") (class "Default")
      (node (ref "U1") (pin "33") (pinfunction "SOSCI/RP4(1)/CN1/RB4_33") (pintype "bidirectional"))
    )
    (net (code "96") (name "unconnected-(U1-SOSCO{slash}T1CK{slash}CN0{slash}RA4-Pad34)") (class "Default")
      (node (ref "U1") (pin "34") (pinfunction "SOSCO/T1CK/CN0/RA4_34") (pintype "bidirectional"))
    )
    (net (code "97") (name "unconnected-(U1-TCK{slash}PMA7{slash}RA7*-Pad13)") (class "Default")
      (node (ref "U1") (pin "13") (pinfunction "TCK/PMA7/RA7*_13") (pintype "bidirectional"))
    )
    (net (code "98") (name "unconnected-(U1-TMS{slash}PMA10{slash}RA10*-Pad12)") (class "Default")
      (node (ref "U1") (pin "12") (pinfunction "TMS/PMA10/RA10*_12") (pintype "bidirectional"))
    )
    (net (code "99") (name "unconnected-(U8-CTS-Pad11)") (class "Default")
      (node (ref "U8") (pin "11") (pinfunction "CTS_11") (pintype "bidirectional"))
    )
    (net (code "100") (name "unconnected-(U8-DTR-Pad2)") (class "Default")
      (node (ref "U8") (pin "2") (pinfunction "DTR_2") (pintype "bidirectional"))
    )
    (net (code "101") (name "unconnected-(U8-RTS-Pad3)") (class "Default")
      (node (ref "U8") (pin "3") (pinfunction "RTS_3") (pintype "bidirectional"))
    )
    (net (code "102") (name "unconnected-(U9-~{MR}-Pad3)") (class "Default")
      (node (ref "U9") (pin "3") (pinfunction "~{MR}_3") (pintype "bidirectional"))
    )
  )
)
